# Sensor_Node_V2.net
KiCad netlist of a schematic drawn in EAGLE
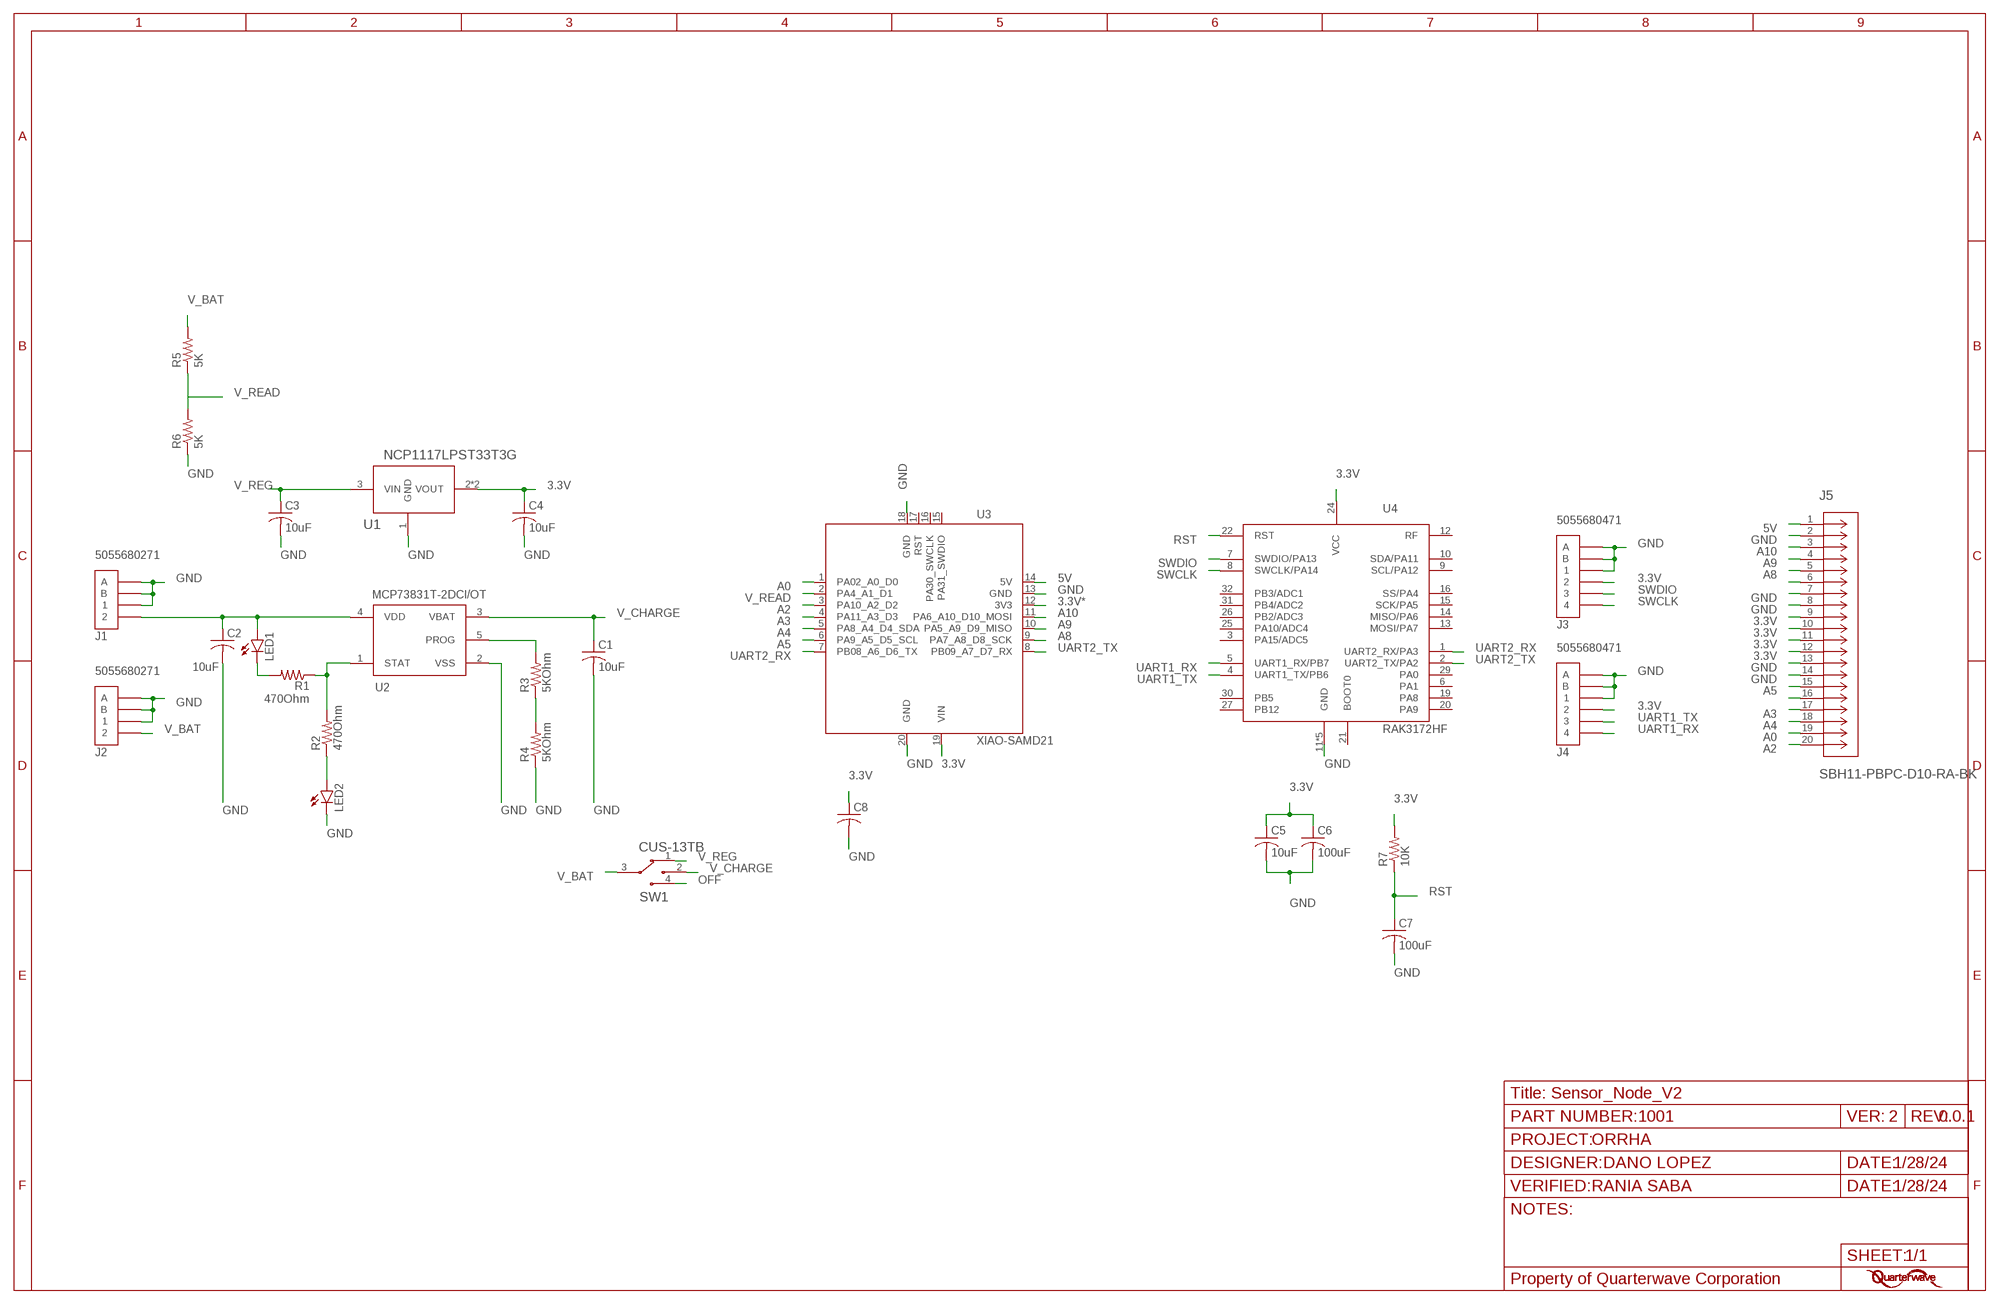
[diagram p0: schematic, sheet 1]

(export (version "E")
  (design (tool "Eeschema 10.0.6"))
  (components
    (comp (ref "C1")
      (value "10uF")
      (footprint "eagle-import:C0805")
      (libsource (lib "eagle-import") (part "C-USC0805"))
    )
    (comp (ref "C2")
      (value "10uF")
      (footprint "eagle-import:C0805")
      (libsource (lib "eagle-import") (part "C-USC0805"))
    )
    (comp (ref "C3")
      (value "10uF")
      (footprint "eagle-import:C0805")
      (libsource (lib "eagle-import") (part "C-USC0805"))
    )
    (comp (ref "C4")
      (value "10uF")
      (footprint "eagle-import:C0805")
      (libsource (lib "eagle-import") (part "C-USC0805"))
    )
    (comp (ref "C5")
      (value "10uF")
      (footprint "eagle-import:C0805")
      (libsource (lib "eagle-import") (part "C-USC0805"))
    )
    (comp (ref "C6")
      (value "100uF")
      (footprint "eagle-import:C0805")
      (libsource (lib "eagle-import") (part "C-USC0805"))
    )
    (comp (ref "C7")
      (value "100uF")
      (footprint "eagle-import:C0805")
      (libsource (lib "eagle-import") (part "C-USC0805"))
    )
    (comp (ref "C8")
      (value "C-USC0805")
      (footprint "eagle-import:C0805")
      (libsource (lib "eagle-import") (part "C-USC0805"))
    )
    (comp (ref "FRAME1")
      (value "STANDARDSTD_INFO_HW14_W30")
      (footprint "eagle-import:STD_INFO_H14_W30")
      (fields
        (field (name "COMPLETE_DATE") "1/28/24")
        (field (name "DESIGNER_NAME") "DANO LOPEZ")
        (field (name "PART_NUMBER") "1001")
        (field (name "PROJECT_NAME") "ORRHA")
        (field (name "R") "0.0.1")
        (field (name "V") "2")
        (field (name "VERIFIER_NAME") "RANIA SABA")
        (field (name "VERIFY_DATE") "1/28/24")
      )
      (libsource (lib "eagle-import") (part "STANDARDSTD_INFO_HW14_W30"))
    )
    (comp (ref "J1")
      (value "5055680271")
      (footprint "eagle-import:5055680271")
      (libsource (lib "eagle-import") (part "5055680271"))
    )
    (comp (ref "J2")
      (value "5055680271")
      (footprint "eagle-import:5055680271")
      (libsource (lib "eagle-import") (part "5055680271"))
    )
    (comp (ref "J3")
      (value "5055680471")
      (footprint "eagle-import:5055680471")
      (libsource (lib "eagle-import") (part "5055680471"))
    )
    (comp (ref "J4")
      (value "5055680471")
      (footprint "eagle-import:5055680471")
      (libsource (lib "eagle-import") (part "5055680471"))
    )
    (comp (ref "J5")
      (value "SBH11-PBPC-D10-RA-BK")
      (footprint "eagle-import:CONN20_D10-RA-BK_SUL")
      (fields (field (name "COPYRIGHT") "Copyright (C) 2024 Ultra Librarian. All rights reserved."))
      (libsource (lib "eagle-import") (part "SBH11-PBPC-D10-RA-BK"))
    )
    (comp (ref "LED1")
      (value "LEDCHIPLED_0603")
      (footprint "eagle-import:CHIPLED_0603")
      (libsource (lib "eagle-import") (part "LEDCHIPLED_0603"))
    )
    (comp (ref "LED2")
      (value "LEDCHIPLED_0603")
      (footprint "eagle-import:CHIPLED_0603")
      (libsource (lib "eagle-import") (part "LEDCHIPLED_0603"))
    )
    (comp (ref "R1")
      (value "470Ohm")
      (footprint "eagle-import:R0805")
      (libsource (lib "eagle-import") (part "R-US_R0805"))
    )
    (comp (ref "R2")
      (value "470Ohm")
      (footprint "eagle-import:R0805")
      (libsource (lib "eagle-import") (part "R-US_R0805"))
    )
    (comp (ref "R3")
      (value "5KOhm")
      (footprint "eagle-import:R0805")
      (libsource (lib "eagle-import") (part "R-US_R0805"))
    )
    (comp (ref "R4")
      (value "5KOhm")
      (footprint "eagle-import:R0805")
      (libsource (lib "eagle-import") (part "R-US_R0805"))
    )
    (comp (ref "R5")
      (value "5K")
      (footprint "eagle-import:R0805")
      (libsource (lib "eagle-import") (part "R-US_R0805"))
    )
    (comp (ref "R6")
      (value "5K")
      (footprint "eagle-import:R0805")
      (libsource (lib "eagle-import") (part "R-US_R0805"))
    )
    (comp (ref "R7")
      (value "10K")
      (footprint "eagle-import:R0805")
      (libsource (lib "eagle-import") (part "R-US_R0805"))
    )
    (comp (ref "SW1")
      (value "CUS-13TB")
      (footprint "eagle-import:CUS-13TB_NDC")
      (fields (field (name "COPYRIGHT") "Copyright (C) 2021 Ultra Librarian. All rights reserved."))
      (libsource (lib "eagle-import") (part "CUS-13TB"))
    )
    (comp (ref "U1")
      (value "NCP1117LPST33T3G")
      (footprint "eagle-import:SOT-223_DIO")
      (libsource (lib "eagle-import") (part "NCP1117LPST33T3G"))
    )
    (comp (ref "U2")
      (value "MCP73831T-2DCI/OT")
      (footprint "eagle-import:SOT-23-5_MC_MCH")
      (fields (field (name "COPYRIGHT") "Copyright (C) 2022 Ultra Librarian. All rights reserved."))
      (libsource (lib "eagle-import") (part "MCP73831T-2DCI/OT"))
    )
    (comp (ref "U3")
      (value "XIAO-SAMD21")
      (footprint "eagle-import:XIAO-SAMD21_RP2040-MODULE14P-2.54-21X17.8MM")
      (libsource (lib "eagle-import") (part "XIAO-SAMD21"))
    )
    (comp (ref "U4")
      (value "RAK3172HF")
      (footprint "eagle-import:RAK3172")
      (fields (field (name "MF") "Shenzhen RAKwireless Technology Co.,Ltd.") (field (name "MP") "RAK3172"))
      (libsource (lib "eagle-import") (part "RAK3172HF"))
    )
  )
  (nets
    (net (code "1") (name "/3.3V") (class "Default")
      (node (ref "C4") (pin "1") (pinfunction "1_1") (pintype "passive"))
      (node (ref "C5") (pin "1") (pinfunction "1_1") (pintype "passive"))
      (node (ref "C6") (pin "1") (pinfunction "1_1") (pintype "passive"))
      (node (ref "C8") (pin "1") (pinfunction "1_1") (pintype "passive"))
      (node (ref "J3") (pin "2") (pinfunction "2_2") (pintype "bidirectional"))
      (node (ref "J4") (pin "2") (pinfunction "2_2") (pintype "bidirectional"))
      (node (ref "J5") (pin "10") (pinfunction "10_10") (pintype "passive"))
      (node (ref "J5") (pin "11") (pinfunction "11_11") (pintype "passive"))
      (node (ref "J5") (pin "12") (pinfunction "12_12") (pintype "passive"))
      (node (ref "J5") (pin "9") (pinfunction "9_9") (pintype "passive"))
      (node (ref "R7") (pin "2") (pinfunction "2_2") (pintype "passive"))
      (node (ref "U1") (pin "2") (pinfunction "VOUT_2") (pintype "output"))
      (node (ref "U1") (pin "4") (pinfunction "VOUT_4") (pintype "output"))
      (node (ref "U3") (pin "19") (pinfunction "VIN_19") (pintype "bidirectional"))
      (node (ref "U4") (pin "24") (pinfunction "VCC_24") (pintype "power_in"))
    )
    (net (code "2") (name "/3.3V*") (class "Default")
      (node (ref "U3") (pin "12") (pinfunction "3V3_12") (pintype "bidirectional"))
    )
    (net (code "3") (name "/5V") (class "Default")
      (node (ref "J5") (pin "1") (pinfunction "1_1") (pintype "passive"))
      (node (ref "U3") (pin "14") (pinfunction "5V_14") (pintype "bidirectional"))
    )
    (net (code "4") (name "/A0") (class "Default")
      (node (ref "J5") (pin "19") (pinfunction "19_19") (pintype "passive"))
      (node (ref "U3") (pin "1") (pinfunction "PA02_A0_D0_1") (pintype "bidirectional"))
    )
    (net (code "5") (name "/A2") (class "Default")
      (node (ref "J5") (pin "20") (pinfunction "20_20") (pintype "passive"))
      (node (ref "U3") (pin "3") (pinfunction "PA10_A2_D2_3") (pintype "bidirectional"))
    )
    (net (code "6") (name "/A3") (class "Default")
      (node (ref "J5") (pin "17") (pinfunction "17_17") (pintype "passive"))
      (node (ref "U3") (pin "4") (pinfunction "PA11_A3_D3_4") (pintype "bidirectional"))
    )
    (net (code "7") (name "/A4") (class "Default")
      (node (ref "J5") (pin "18") (pinfunction "18_18") (pintype "passive"))
      (node (ref "U3") (pin "5") (pinfunction "PA8_A4_D4_SDA_5") (pintype "bidirectional"))
    )
    (net (code "8") (name "/A5") (class "Default")
      (node (ref "J5") (pin "15") (pinfunction "15_15") (pintype "passive"))
      (node (ref "U3") (pin "6") (pinfunction "PA9_A5_D5_SCL_6") (pintype "bidirectional"))
    )
    (net (code "9") (name "/A8") (class "Default")
      (node (ref "J5") (pin "5") (pinfunction "5_5") (pintype "passive"))
      (node (ref "U3") (pin "9") (pinfunction "PA7_A8_D8_SCK_9") (pintype "bidirectional"))
    )
    (net (code "10") (name "/A9") (class "Default")
      (node (ref "J5") (pin "4") (pinfunction "4_4") (pintype "passive"))
      (node (ref "U3") (pin "10") (pinfunction "PA5_A9_D9_MISO_10") (pintype "bidirectional"))
    )
    (net (code "11") (name "/A10") (class "Default")
      (node (ref "J5") (pin "3") (pinfunction "3_3") (pintype "passive"))
      (node (ref "U3") (pin "11") (pinfunction "PA6_A10_D10_MOSI_11") (pintype "bidirectional"))
    )
    (net (code "12") (name "/GND") (class "Default")
      (node (ref "C1") (pin "2") (pinfunction "2_2") (pintype "passive"))
      (node (ref "C2") (pin "2") (pinfunction "2_2") (pintype "passive"))
      (node (ref "C3") (pin "2") (pinfunction "2_2") (pintype "passive"))
      (node (ref "C4") (pin "2") (pinfunction "2_2") (pintype "passive"))
      (node (ref "C5") (pin "2") (pinfunction "2_2") (pintype "passive"))
      (node (ref "C6") (pin "2") (pinfunction "2_2") (pintype "passive"))
      (node (ref "C7") (pin "2") (pinfunction "2_2") (pintype "passive"))
      (node (ref "C8") (pin "2") (pinfunction "2_2") (pintype "passive"))
      (node (ref "J1") (pin "1") (pinfunction "1_1") (pintype "bidirectional"))
      (node (ref "J1") (pin "A") (pinfunction "A_A") (pintype "bidirectional"))
      (node (ref "J1") (pin "B") (pinfunction "B_B") (pintype "bidirectional"))
      (node (ref "J2") (pin "1") (pinfunction "1_1") (pintype "bidirectional"))
      (node (ref "J2") (pin "A") (pinfunction "A_A") (pintype "bidirectional"))
      (node (ref "J2") (pin "B") (pinfunction "B_B") (pintype "bidirectional"))
      (node (ref "J3") (pin "1") (pinfunction "1_1") (pintype "bidirectional"))
      (node (ref "J3") (pin "A") (pinfunction "A_A") (pintype "bidirectional"))
      (node (ref "J3") (pin "B") (pinfunction "B_B") (pintype "bidirectional"))
      (node (ref "J4") (pin "1") (pinfunction "1_1") (pintype "bidirectional"))
      (node (ref "J4") (pin "A") (pinfunction "A_A") (pintype "bidirectional"))
      (node (ref "J4") (pin "B") (pinfunction "B_B") (pintype "bidirectional"))
      (node (ref "J5") (pin "13") (pinfunction "13_13") (pintype "passive"))
      (node (ref "J5") (pin "14") (pinfunction "14_14") (pintype "passive"))
      (node (ref "J5") (pin "2") (pinfunction "2_2") (pintype "passive"))
      (node (ref "J5") (pin "7") (pinfunction "7_7") (pintype "passive"))
      (node (ref "J5") (pin "8") (pinfunction "8_8") (pintype "passive"))
      (node (ref "LED2") (pin "C") (pinfunction "C_C") (pintype "passive"))
      (node (ref "R4") (pin "1") (pinfunction "1_1") (pintype "passive"))
      (node (ref "R6") (pin "1") (pinfunction "1_1") (pintype "passive"))
      (node (ref "U1") (pin "1") (pinfunction "GND_1") (pintype "power_in"))
      (node (ref "U2") (pin "2") (pinfunction "VSS_2") (pintype "passive"))
      (node (ref "U3") (pin "13") (pinfunction "GND_13") (pintype "bidirectional"))
      (node (ref "U3") (pin "18") (pinfunction "GND_18") (pintype "bidirectional"))
      (node (ref "U3") (pin "20") (pinfunction "GND_20") (pintype "bidirectional"))
      (node (ref "U4") (pin "11") (pinfunction "GND_11") (pintype "power_in"))
      (node (ref "U4") (pin "17") (pinfunction "GND_17") (pintype "power_in"))
      (node (ref "U4") (pin "18") (pinfunction "GND_18") (pintype "power_in"))
      (node (ref "U4") (pin "23") (pinfunction "GND_23") (pintype "power_in"))
      (node (ref "U4") (pin "28") (pinfunction "GND_28") (pintype "power_in"))
    )
    (net (code "13") (name "/OFF") (class "Default")
      (node (ref "SW1") (pin "4") (pinfunction "4_4") (pintype "passive"))
    )
    (net (code "14") (name "/RST") (class "Default")
      (node (ref "C7") (pin "1") (pinfunction "1_1") (pintype "passive"))
      (node (ref "R7") (pin "1") (pinfunction "1_1") (pintype "passive"))
      (node (ref "U4") (pin "22") (pinfunction "RST_22") (pintype "input"))
    )
    (net (code "15") (name "/SWCLK") (class "Default")
      (node (ref "J3") (pin "4") (pinfunction "4_4") (pintype "bidirectional"))
      (node (ref "U4") (pin "8") (pinfunction "SWCLK/PA14_8") (pintype "bidirectional"))
    )
    (net (code "16") (name "/SWDIO") (class "Default")
      (node (ref "J3") (pin "3") (pinfunction "3_3") (pintype "bidirectional"))
      (node (ref "U4") (pin "7") (pinfunction "SWDIO/PA13_7") (pintype "bidirectional"))
    )
    (net (code "17") (name "/UART1_RX") (class "Default")
      (node (ref "J4") (pin "4") (pinfunction "4_4") (pintype "bidirectional"))
      (node (ref "U4") (pin "5") (pinfunction "UART1_RX/PB7_5") (pintype "bidirectional"))
    )
    (net (code "18") (name "/UART1_TX") (class "Default")
      (node (ref "J4") (pin "3") (pinfunction "3_3") (pintype "bidirectional"))
      (node (ref "U4") (pin "4") (pinfunction "UART1_TX/PB6_4") (pintype "bidirectional"))
    )
    (net (code "19") (name "/UART2_RX") (class "Default")
      (node (ref "U3") (pin "7") (pinfunction "PB08_A6_D6_TX_7") (pintype "bidirectional"))
      (node (ref "U4") (pin "1") (pinfunction "UART2_RX/PA3_1") (pintype "bidirectional"))
    )
    (net (code "20") (name "/UART2_TX") (class "Default")
      (node (ref "U3") (pin "8") (pinfunction "PB09_A7_D7_RX_8") (pintype "bidirectional"))
      (node (ref "U4") (pin "2") (pinfunction "UART2_TX/PA2_2") (pintype "bidirectional"))
    )
    (net (code "21") (name "/V_BAT") (class "Default")
      (node (ref "J2") (pin "2") (pinfunction "2_2") (pintype "bidirectional"))
      (node (ref "R5") (pin "2") (pinfunction "2_2") (pintype "passive"))
      (node (ref "SW1") (pin "3") (pinfunction "3_3") (pintype "passive"))
    )
    (net (code "22") (name "/V_CHARGE") (class "Default")
      (node (ref "C1") (pin "1") (pinfunction "1_1") (pintype "passive"))
      (node (ref "SW1") (pin "2") (pinfunction "2_2") (pintype "passive"))
      (node (ref "U2") (pin "3") (pinfunction "VBAT_3") (pintype "passive"))
    )
    (net (code "23") (name "/V_READ") (class "Default")
      (node (ref "R5") (pin "1") (pinfunction "1_1") (pintype "passive"))
      (node (ref "R6") (pin "2") (pinfunction "2_2") (pintype "passive"))
      (node (ref "U3") (pin "2") (pinfunction "PA4_A1_D1_2") (pintype "bidirectional"))
    )
    (net (code "24") (name "/V_REG") (class "Default")
      (node (ref "C3") (pin "1") (pinfunction "1_1") (pintype "passive"))
      (node (ref "SW1") (pin "1") (pinfunction "1_1") (pintype "passive"))
      (node (ref "U1") (pin "3") (pinfunction "VIN_3") (pintype "input"))
    )
    (net (code "25") (name "Net-(LED1-PadC)") (class "Default")
      (node (ref "LED1") (pin "C") (pinfunction "C_C") (pintype "passive"))
      (node (ref "R1") (pin "2") (pinfunction "2_2") (pintype "passive"))
    )
    (net (code "26") (name "Net-(LED2-PadA)") (class "Default")
      (node (ref "LED2") (pin "A") (pinfunction "A_A") (pintype "passive"))
      (node (ref "R2") (pin "1") (pinfunction "1_1") (pintype "passive"))
    )
    (net (code "27") (name "Net-(R3-Pad1)") (class "Default")
      (node (ref "R3") (pin "1") (pinfunction "1_1") (pintype "passive"))
      (node (ref "R4") (pin "2") (pinfunction "2_2") (pintype "passive"))
    )
    (net (code "28") (name "Net-(U2-PROG)") (class "Default")
      (node (ref "R3") (pin "2") (pinfunction "2_2") (pintype "passive"))
      (node (ref "U2") (pin "5") (pinfunction "PROG_5") (pintype "passive"))
    )
    (net (code "29") (name "Net-(U2-STAT)") (class "Default")
      (node (ref "R1") (pin "1") (pinfunction "1_1") (pintype "passive"))
      (node (ref "R2") (pin "2") (pinfunction "2_2") (pintype "passive"))
      (node (ref "U2") (pin "1") (pinfunction "STAT_1") (pintype "passive"))
    )
    (net (code "30") (name "Net-(U2-VDD)") (class "Default")
      (node (ref "C2") (pin "1") (pinfunction "1_1") (pintype "passive"))
      (node (ref "J1") (pin "2") (pinfunction "2_2") (pintype "bidirectional"))
      (node (ref "LED1") (pin "A") (pinfunction "A_A") (pintype "passive"))
      (node (ref "U2") (pin "4") (pinfunction "VDD_4") (pintype "passive"))
    )
    (net (code "31") (name "unconnected-(J5-Pad6)") (class "Default")
      (node (ref "J5") (pin "6") (pinfunction "6_6") (pintype "passive"))
    )
    (net (code "32") (name "unconnected-(J5-Pad16)") (class "Default")
      (node (ref "J5") (pin "16") (pinfunction "16_16") (pintype "passive"))
    )
    (net (code "33") (name "unconnected-(U3-PA30_SWCLK-Pad16)") (class "Default")
      (node (ref "U3") (pin "16") (pinfunction "PA30_SWCLK_16") (pintype "bidirectional"))
    )
    (net (code "34") (name "unconnected-(U3-PA31_SWDIO-Pad15)") (class "Default")
      (node (ref "U3") (pin "15") (pinfunction "PA31_SWDIO_15") (pintype "bidirectional"))
    )
    (net (code "35") (name "unconnected-(U3-RST-Pad17)") (class "Default")
      (node (ref "U3") (pin "17") (pinfunction "RST_17") (pintype "bidirectional"))
    )
    (net (code "36") (name "unconnected-(U4-BOOT0-Pad21)") (class "Default")
      (node (ref "U4") (pin "21") (pinfunction "BOOT0_21") (pintype "input"))
    )
    (net (code "37") (name "unconnected-(U4-MISO{slash}PA6-Pad14)") (class "Default")
      (node (ref "U4") (pin "14") (pinfunction "MISO/PA6_14") (pintype "bidirectional"))
    )
    (net (code "38") (name "unconnected-(U4-MOSI{slash}PA7-Pad13)") (class "Default")
      (node (ref "U4") (pin "13") (pinfunction "MOSI/PA7_13") (pintype "bidirectional"))
    )
    (net (code "39") (name "unconnected-(U4-PA0-Pad29)") (class "Default")
      (node (ref "U4") (pin "29") (pinfunction "PA0_29") (pintype "bidirectional"))
    )
    (net (code "40") (name "unconnected-(U4-PA1-Pad6)") (class "Default")
      (node (ref "U4") (pin "6") (pinfunction "PA1_6") (pintype "bidirectional"))
    )
    (net (code "41") (name "unconnected-(U4-PA8-Pad19)") (class "Default")
      (node (ref "U4") (pin "19") (pinfunction "PA8_19") (pintype "bidirectional"))
    )
    (net (code "42") (name "unconnected-(U4-PA9-Pad20)") (class "Default")
      (node (ref "U4") (pin "20") (pinfunction "PA9_20") (pintype "bidirectional"))
    )
    (net (code "43") (name "unconnected-(U4-PA10{slash}ADC4-Pad25)") (class "Default")
      (node (ref "U4") (pin "25") (pinfunction "PA10/ADC4_25") (pintype "bidirectional"))
    )
    (net (code "44") (name "unconnected-(U4-PA15{slash}ADC5-Pad3)") (class "Default")
      (node (ref "U4") (pin "3") (pinfunction "PA15/ADC5_3") (pintype "bidirectional"))
    )
    (net (code "45") (name "unconnected-(U4-PB2{slash}ADC3-Pad26)") (class "Default")
      (node (ref "U4") (pin "26") (pinfunction "PB2/ADC3_26") (pintype "bidirectional"))
    )
    (net (code "46") (name "unconnected-(U4-PB3{slash}ADC1-Pad32)") (class "Default")
      (node (ref "U4") (pin "32") (pinfunction "PB3/ADC1_32") (pintype "bidirectional"))
    )
    (net (code "47") (name "unconnected-(U4-PB4{slash}ADC2-Pad31)") (class "Default")
      (node (ref "U4") (pin "31") (pinfunction "PB4/ADC2_31") (pintype "bidirectional"))
    )
    (net (code "48") (name "unconnected-(U4-PB5-Pad30)") (class "Default")
      (node (ref "U4") (pin "30") (pinfunction "PB5_30") (pintype "bidirectional"))
    )
    (net (code "49") (name "unconnected-(U4-PB12-Pad27)") (class "Default")
      (node (ref "U4") (pin "27") (pinfunction "PB12_27") (pintype "bidirectional"))
    )
    (net (code "50") (name "unconnected-(U4-RF-Pad12)") (class "Default")
      (node (ref "U4") (pin "12") (pinfunction "RF_12") (pintype "output"))
    )
    (net (code "51") (name "unconnected-(U4-SCK{slash}PA5-Pad15)") (class "Default")
      (node (ref "U4") (pin "15") (pinfunction "SCK/PA5_15") (pintype "bidirectional"))
    )
    (net (code "52") (name "unconnected-(U4-SCL{slash}PA12-Pad9)") (class "Default")
      (node (ref "U4") (pin "9") (pinfunction "SCL/PA12_9") (pintype "bidirectional"))
    )
    (net (code "53") (name "unconnected-(U4-SDA{slash}PA11-Pad10)") (class "Default")
      (node (ref "U4") (pin "10") (pinfunction "SDA/PA11_10") (pintype "bidirectional"))
    )
    (net (code "54") (name "unconnected-(U4-SS{slash}PA4-Pad16)") (class "Default")
      (node (ref "U4") (pin "16") (pinfunction "SS/PA4_16") (pintype "bidirectional"))
    )
  )
)
